# 06_-_DRAM.net
KiCad netlist of a schematic drawn in Altium Designer
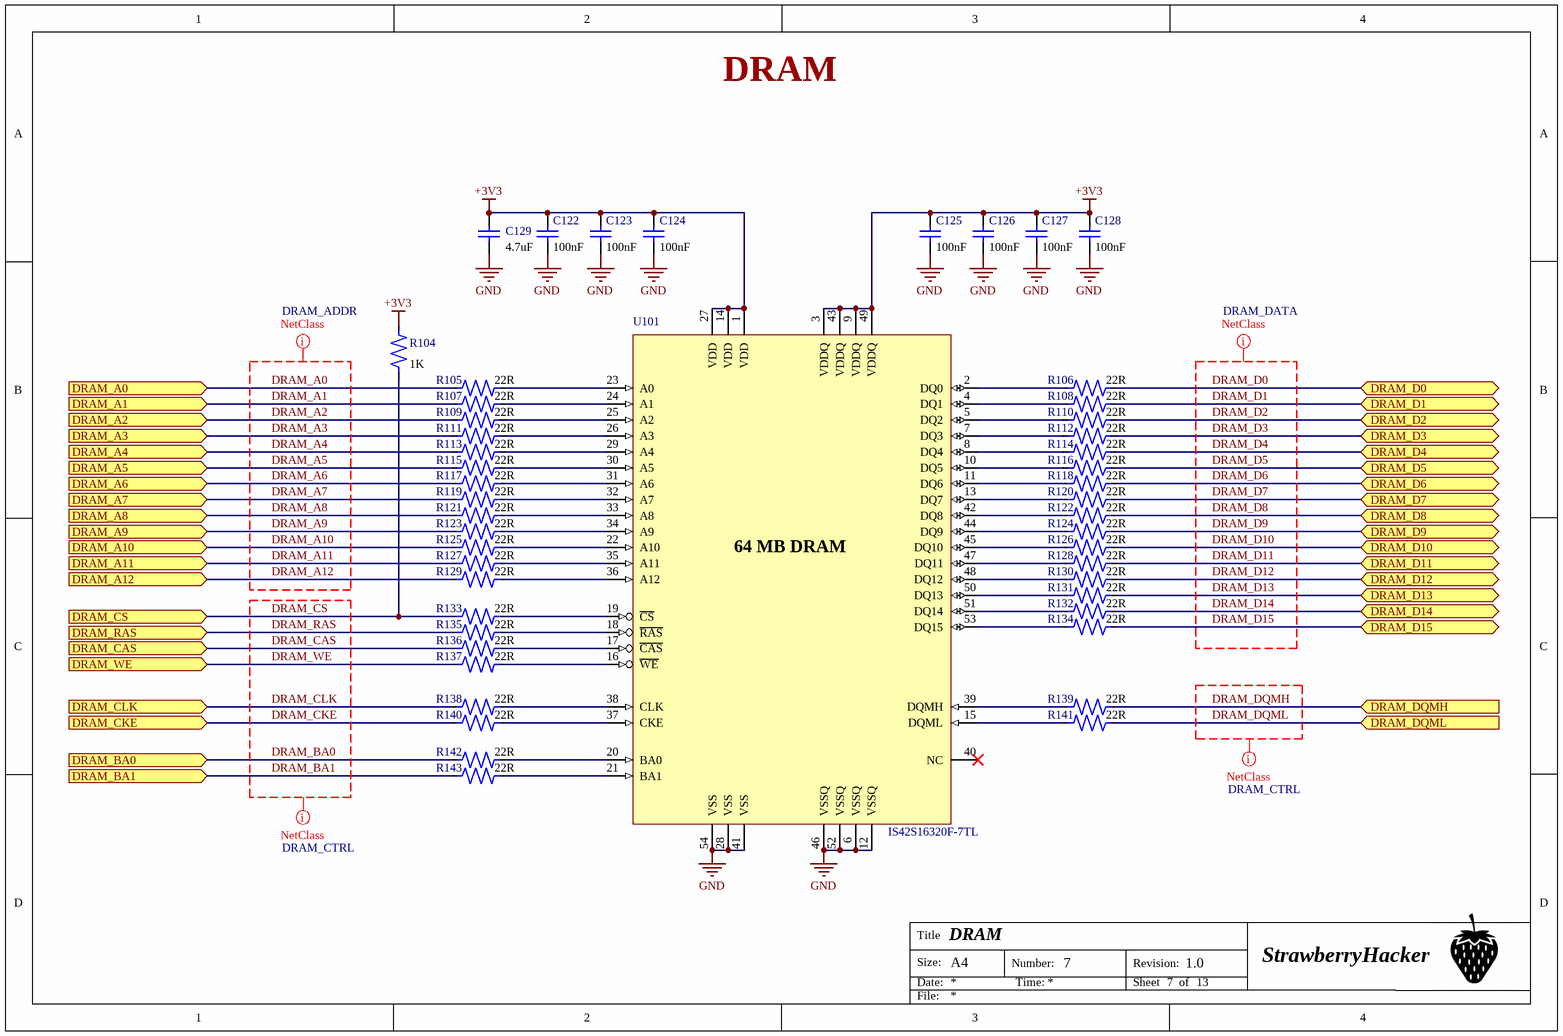
[diagram p0: [06] - DRAM.SchDoc]

(export (version "E")
  (design (tool "Eeschema 10.0.6"))
  (components
    (comp (ref "C122")
      (value "100nF")
      (footprint "C0402")
      (description "C0402")
      (fields (field (name "Comment") "04023C103KAT2A"))
      (libsource (lib "Passive components") (part "04023C103KAT2A"))
    )
    (comp (ref "C123")
      (value "100nF")
      (footprint "C0402")
      (description "C0402")
      (fields (field (name "Comment") "04023C103KAT2A"))
      (libsource (lib "Passive components") (part "04023C103KAT2A"))
    )
    (comp (ref "C124")
      (value "100nF")
      (footprint "C0402")
      (description "C0402")
      (fields (field (name "Comment") "04023C103KAT2A"))
      (libsource (lib "Passive components") (part "04023C103KAT2A"))
    )
    (comp (ref "C125")
      (value "100nF")
      (footprint "C0402")
      (description "C0402")
      (fields (field (name "Comment") "04023C103KAT2A"))
      (libsource (lib "Passive components") (part "04023C103KAT2A"))
    )
    (comp (ref "C126")
      (value "100nF")
      (footprint "C0402")
      (description "C0402")
      (fields (field (name "Comment") "04023C103KAT2A"))
      (libsource (lib "Passive components") (part "04023C103KAT2A"))
    )
    (comp (ref "C127")
      (value "100nF")
      (footprint "C0402")
      (description "C0402")
      (fields (field (name "Comment") "04023C103KAT2A"))
      (libsource (lib "Passive components") (part "04023C103KAT2A"))
    )
    (comp (ref "C128")
      (value "100nF")
      (footprint "C0402")
      (description "C0402")
      (fields (field (name "Comment") "04023C103KAT2A"))
      (libsource (lib "Passive components") (part "04023C103KAT2A"))
    )
    (comp (ref "C129")
      (value "4.7uF")
      (footprint "C0402")
      (description "C0402")
      (fields (field (name "Comment") "04023C103KAT2A"))
      (libsource (lib "Passive components") (part "04023C103KAT2A"))
    )
    (comp (ref "R104")
      (value "1K")
      (footprint "R0402")
      (description "R0402")
      (fields (field (name "Comment") "CRCW04020000Z0ED"))
      (libsource (lib "Passive components") (part "CRCW04020000Z0ED"))
    )
    (comp (ref "R105")
      (value "22R")
      (footprint "R0402")
      (description "R0402")
      (fields (field (name "Comment") "CRCW04020000Z0ED"))
      (libsource (lib "Passive components") (part "CRCW04020000Z0ED"))
    )
    (comp (ref "R106")
      (value "22R")
      (footprint "R0402")
      (description "R0402")
      (fields (field (name "Comment") "CRCW04020000Z0ED"))
      (libsource (lib "Passive components") (part "CRCW04020000Z0ED"))
    )
    (comp (ref "R107")
      (value "22R")
      (footprint "R0402")
      (description "R0402")
      (fields (field (name "Comment") "CRCW04020000Z0ED"))
      (libsource (lib "Passive components") (part "CRCW04020000Z0ED"))
    )
    (comp (ref "R108")
      (value "22R")
      (footprint "R0402")
      (description "R0402")
      (fields (field (name "Comment") "CRCW04020000Z0ED"))
      (libsource (lib "Passive components") (part "CRCW04020000Z0ED"))
    )
    (comp (ref "R109")
      (value "22R")
      (footprint "R0402")
      (description "R0402")
      (fields (field (name "Comment") "CRCW04020000Z0ED"))
      (libsource (lib "Passive components") (part "CRCW04020000Z0ED"))
    )
    (comp (ref "R110")
      (value "22R")
      (footprint "R0402")
      (description "R0402")
      (fields (field (name "Comment") "CRCW04020000Z0ED"))
      (libsource (lib "Passive components") (part "CRCW04020000Z0ED"))
    )
    (comp (ref "R111")
      (value "22R")
      (footprint "R0402")
      (description "R0402")
      (fields (field (name "Comment") "CRCW04020000Z0ED"))
      (libsource (lib "Passive components") (part "CRCW04020000Z0ED"))
    )
    (comp (ref "R112")
      (value "22R")
      (footprint "R0402")
      (description "R0402")
      (fields (field (name "Comment") "CRCW04020000Z0ED"))
      (libsource (lib "Passive components") (part "CRCW04020000Z0ED"))
    )
    (comp (ref "R113")
      (value "22R")
      (footprint "R0402")
      (description "R0402")
      (fields (field (name "Comment") "CRCW04020000Z0ED"))
      (libsource (lib "Passive components") (part "CRCW04020000Z0ED"))
    )
    (comp (ref "R114")
      (value "22R")
      (footprint "R0402")
      (description "R0402")
      (fields (field (name "Comment") "CRCW04020000Z0ED"))
      (libsource (lib "Passive components") (part "CRCW04020000Z0ED"))
    )
    (comp (ref "R115")
      (value "22R")
      (footprint "R0402")
      (description "R0402")
      (fields (field (name "Comment") "CRCW04020000Z0ED"))
      (libsource (lib "Passive components") (part "CRCW04020000Z0ED"))
    )
    (comp (ref "R116")
      (value "22R")
      (footprint "R0402")
      (description "R0402")
      (fields (field (name "Comment") "CRCW04020000Z0ED"))
      (libsource (lib "Passive components") (part "CRCW04020000Z0ED"))
    )
    (comp (ref "R117")
      (value "22R")
      (footprint "R0402")
      (description "R0402")
      (fields (field (name "Comment") "CRCW04020000Z0ED"))
      (libsource (lib "Passive components") (part "CRCW04020000Z0ED"))
    )
    (comp (ref "R118")
      (value "22R")
      (footprint "R0402")
      (description "R0402")
      (fields (field (name "Comment") "CRCW04020000Z0ED"))
      (libsource (lib "Passive components") (part "CRCW04020000Z0ED"))
    )
    (comp (ref "R119")
      (value "22R")
      (footprint "R0402")
      (description "R0402")
      (fields (field (name "Comment") "CRCW04020000Z0ED"))
      (libsource (lib "Passive components") (part "CRCW04020000Z0ED"))
    )
    (comp (ref "R120")
      (value "22R")
      (footprint "R0402")
      (description "R0402")
      (fields (field (name "Comment") "CRCW04020000Z0ED"))
      (libsource (lib "Passive components") (part "CRCW04020000Z0ED"))
    )
    (comp (ref "R121")
      (value "22R")
      (footprint "R0402")
      (description "R0402")
      (fields (field (name "Comment") "CRCW04020000Z0ED"))
      (libsource (lib "Passive components") (part "CRCW04020000Z0ED"))
    )
    (comp (ref "R122")
      (value "22R")
      (footprint "R0402")
      (description "R0402")
      (fields (field (name "Comment") "CRCW04020000Z0ED"))
      (libsource (lib "Passive components") (part "CRCW04020000Z0ED"))
    )
    (comp (ref "R123")
      (value "22R")
      (footprint "R0402")
      (description "R0402")
      (fields (field (name "Comment") "CRCW04020000Z0ED"))
      (libsource (lib "Passive components") (part "CRCW04020000Z0ED"))
    )
    (comp (ref "R124")
      (value "22R")
      (footprint "R0402")
      (description "R0402")
      (fields (field (name "Comment") "CRCW04020000Z0ED"))
      (libsource (lib "Passive components") (part "CRCW04020000Z0ED"))
    )
    (comp (ref "R125")
      (value "22R")
      (footprint "R0402")
      (description "R0402")
      (fields (field (name "Comment") "CRCW04020000Z0ED"))
      (libsource (lib "Passive components") (part "CRCW04020000Z0ED"))
    )
    (comp (ref "R126")
      (value "22R")
      (footprint "R0402")
      (description "R0402")
      (fields (field (name "Comment") "CRCW04020000Z0ED"))
      (libsource (lib "Passive components") (part "CRCW04020000Z0ED"))
    )
    (comp (ref "R127")
      (value "22R")
      (footprint "R0402")
      (description "R0402")
      (fields (field (name "Comment") "CRCW04020000Z0ED"))
      (libsource (lib "Passive components") (part "CRCW04020000Z0ED"))
    )
    (comp (ref "R128")
      (value "22R")
      (footprint "R0402")
      (description "R0402")
      (fields (field (name "Comment") "CRCW04020000Z0ED"))
      (libsource (lib "Passive components") (part "CRCW04020000Z0ED"))
    )
    (comp (ref "R129")
      (value "22R")
      (footprint "R0402")
      (description "R0402")
      (fields (field (name "Comment") "CRCW04020000Z0ED"))
      (libsource (lib "Passive components") (part "CRCW04020000Z0ED"))
    )
    (comp (ref "R130")
      (value "22R")
      (footprint "R0402")
      (description "R0402")
      (fields (field (name "Comment") "CRCW04020000Z0ED"))
      (libsource (lib "Passive components") (part "CRCW04020000Z0ED"))
    )
    (comp (ref "R131")
      (value "22R")
      (footprint "R0402")
      (description "R0402")
      (fields (field (name "Comment") "CRCW04020000Z0ED"))
      (libsource (lib "Passive components") (part "CRCW04020000Z0ED"))
    )
    (comp (ref "R132")
      (value "22R")
      (footprint "R0402")
      (description "R0402")
      (fields (field (name "Comment") "CRCW04020000Z0ED"))
      (libsource (lib "Passive components") (part "CRCW04020000Z0ED"))
    )
    (comp (ref "R133")
      (value "22R")
      (footprint "R0402")
      (description "R0402")
      (fields (field (name "Comment") "CRCW04020000Z0ED"))
      (libsource (lib "Passive components") (part "CRCW04020000Z0ED"))
    )
    (comp (ref "R134")
      (value "22R")
      (footprint "R0402")
      (description "R0402")
      (fields (field (name "Comment") "CRCW04020000Z0ED"))
      (libsource (lib "Passive components") (part "CRCW04020000Z0ED"))
    )
    (comp (ref "R135")
      (value "22R")
      (footprint "R0402")
      (description "R0402")
      (fields (field (name "Comment") "CRCW04020000Z0ED"))
      (libsource (lib "Passive components") (part "CRCW04020000Z0ED"))
    )
    (comp (ref "R136")
      (value "22R")
      (footprint "R0402")
      (description "R0402")
      (fields (field (name "Comment") "CRCW04020000Z0ED"))
      (libsource (lib "Passive components") (part "CRCW04020000Z0ED"))
    )
    (comp (ref "R137")
      (value "22R")
      (footprint "R0402")
      (description "R0402")
      (fields (field (name "Comment") "CRCW04020000Z0ED"))
      (libsource (lib "Passive components") (part "CRCW04020000Z0ED"))
    )
    (comp (ref "R138")
      (value "22R")
      (footprint "R0402")
      (description "R0402")
      (fields (field (name "Comment") "CRCW04020000Z0ED"))
      (libsource (lib "Passive components") (part "CRCW04020000Z0ED"))
    )
    (comp (ref "R139")
      (value "22R")
      (footprint "R0402")
      (description "R0402")
      (fields (field (name "Comment") "CRCW04020000Z0ED"))
      (libsource (lib "Passive components") (part "CRCW04020000Z0ED"))
    )
    (comp (ref "R140")
      (value "22R")
      (footprint "R0402")
      (description "R0402")
      (fields (field (name "Comment") "CRCW04020000Z0ED"))
      (libsource (lib "Passive components") (part "CRCW04020000Z0ED"))
    )
    (comp (ref "R141")
      (value "22R")
      (footprint "R0402")
      (description "R0402")
      (fields (field (name "Comment") "CRCW04020000Z0ED"))
      (libsource (lib "Passive components") (part "CRCW04020000Z0ED"))
    )
    (comp (ref "R142")
      (value "22R")
      (footprint "R0402")
      (description "R0402")
      (fields (field (name "Comment") "CRCW04020000Z0ED"))
      (libsource (lib "Passive components") (part "CRCW04020000Z0ED"))
    )
    (comp (ref "R143")
      (value "22R")
      (footprint "R0402")
      (description "R0402")
      (fields (field (name "Comment") "CRCW04020000Z0ED"))
      (libsource (lib "Passive components") (part "CRCW04020000Z0ED"))
    )
    (comp (ref "U101")
      (value "IS42S16320F-7TL")
      (footprint "IS42S16320F-7TL")
      (description "SDRAM 512Mb 32Mx16 TSOP")
      (libsource (lib "Memory") (part "IS42S16320F-7TL"))
    )
  )
  (nets
    (net (code "1") (name "+3V3") (class "Default")
      (node (ref "C122") (pin "2") (pinfunction "2_2") (pintype "passive"))
      (node (ref "C123") (pin "2") (pinfunction "2_2") (pintype "passive"))
      (node (ref "C124") (pin "2") (pinfunction "2_2") (pintype "passive"))
      (node (ref "C125") (pin "2") (pinfunction "2_2") (pintype "passive"))
      (node (ref "C126") (pin "2") (pinfunction "2_2") (pintype "passive"))
      (node (ref "C127") (pin "2") (pinfunction "2_2") (pintype "passive"))
      (node (ref "C128") (pin "2") (pinfunction "2_2") (pintype "passive"))
      (node (ref "C129") (pin "2") (pinfunction "2_2") (pintype "passive"))
      (node (ref "R104") (pin "2") (pinfunction "3_2") (pintype "passive"))
      (node (ref "U101") (pin "1") (pinfunction "VDD_1") (pintype "power_in"))
      (node (ref "U101") (pin "14") (pinfunction "VDD_14") (pintype "power_in"))
      (node (ref "U101") (pin "27") (pinfunction "VDD_27") (pintype "power_in"))
      (node (ref "U101") (pin "3") (pinfunction "VDDQ_3") (pintype "power_in"))
      (node (ref "U101") (pin "43") (pinfunction "VDDQ_43") (pintype "power_in"))
      (node (ref "U101") (pin "49") (pinfunction "VDDQ_49") (pintype "power_in"))
      (node (ref "U101") (pin "9") (pinfunction "VDDQ_9") (pintype "power_in"))
    )
    (net (code "2") (name "/DRAM_A0") (class "Default")
      (node (ref "R105") (pin "1") (pinfunction "1_1") (pintype "passive"))
    )
    (net (code "3") (name "/DRAM_A1") (class "Default")
      (node (ref "R107") (pin "1") (pinfunction "1_1") (pintype "passive"))
    )
    (net (code "4") (name "/DRAM_A2") (class "Default")
      (node (ref "R109") (pin "1") (pinfunction "1_1") (pintype "passive"))
    )
    (net (code "5") (name "/DRAM_A3") (class "Default")
      (node (ref "R111") (pin "1") (pinfunction "1_1") (pintype "passive"))
    )
    (net (code "6") (name "/DRAM_A4") (class "Default")
      (node (ref "R113") (pin "1") (pinfunction "1_1") (pintype "passive"))
    )
    (net (code "7") (name "/DRAM_A5") (class "Default")
      (node (ref "R115") (pin "1") (pinfunction "1_1") (pintype "passive"))
    )
    (net (code "8") (name "/DRAM_A6") (class "Default")
      (node (ref "R117") (pin "1") (pinfunction "1_1") (pintype "passive"))
    )
    (net (code "9") (name "/DRAM_A7") (class "Default")
      (node (ref "R119") (pin "1") (pinfunction "1_1") (pintype "passive"))
    )
    (net (code "10") (name "/DRAM_A8") (class "Default")
      (node (ref "R121") (pin "1") (pinfunction "1_1") (pintype "passive"))
    )
    (net (code "11") (name "/DRAM_A9") (class "Default")
      (node (ref "R123") (pin "1") (pinfunction "1_1") (pintype "passive"))
    )
    (net (code "12") (name "/DRAM_A10") (class "Default")
      (node (ref "R125") (pin "1") (pinfunction "1_1") (pintype "passive"))
    )
    (net (code "13") (name "/DRAM_A11") (class "Default")
      (node (ref "R127") (pin "1") (pinfunction "1_1") (pintype "passive"))
    )
    (net (code "14") (name "/DRAM_A12") (class "Default")
      (node (ref "R129") (pin "1") (pinfunction "1_1") (pintype "passive"))
    )
    (net (code "15") (name "/DRAM_BA0") (class "Default")
      (node (ref "R142") (pin "1") (pinfunction "1_1") (pintype "passive"))
    )
    (net (code "16") (name "/DRAM_BA1") (class "Default")
      (node (ref "R143") (pin "1") (pinfunction "1_1") (pintype "passive"))
    )
    (net (code "17") (name "/DRAM_CAS") (class "Default")
      (node (ref "R136") (pin "1") (pinfunction "1_1") (pintype "passive"))
    )
    (net (code "18") (name "/DRAM_CKE") (class "Default")
      (node (ref "R140") (pin "1") (pinfunction "1_1") (pintype "passive"))
    )
    (net (code "19") (name "/DRAM_CLK") (class "Default")
      (node (ref "R138") (pin "1") (pinfunction "1_1") (pintype "passive"))
    )
    (net (code "20") (name "/DRAM_CS") (class "Default")
      (node (ref "R104") (pin "1") (pinfunction "1_1") (pintype "passive"))
      (node (ref "R133") (pin "1") (pinfunction "1_1") (pintype "passive"))
    )
    (net (code "21") (name "/DRAM_D0") (class "Default")
      (node (ref "R106") (pin "2") (pinfunction "3_2") (pintype "passive"))
    )
    (net (code "22") (name "/DRAM_D1") (class "Default")
      (node (ref "R108") (pin "2") (pinfunction "3_2") (pintype "passive"))
    )
    (net (code "23") (name "/DRAM_D2") (class "Default")
      (node (ref "R110") (pin "2") (pinfunction "3_2") (pintype "passive"))
    )
    (net (code "24") (name "/DRAM_D3") (class "Default")
      (node (ref "R112") (pin "2") (pinfunction "3_2") (pintype "passive"))
    )
    (net (code "25") (name "/DRAM_D4") (class "Default")
      (node (ref "R114") (pin "2") (pinfunction "3_2") (pintype "passive"))
    )
    (net (code "26") (name "/DRAM_D5") (class "Default")
      (node (ref "R116") (pin "2") (pinfunction "3_2") (pintype "passive"))
    )
    (net (code "27") (name "/DRAM_D6") (class "Default")
      (node (ref "R118") (pin "2") (pinfunction "3_2") (pintype "passive"))
    )
    (net (code "28") (name "/DRAM_D7") (class "Default")
      (node (ref "R120") (pin "2") (pinfunction "3_2") (pintype "passive"))
    )
    (net (code "29") (name "/DRAM_D8") (class "Default")
      (node (ref "R122") (pin "2") (pinfunction "3_2") (pintype "passive"))
    )
    (net (code "30") (name "/DRAM_D9") (class "Default")
      (node (ref "R124") (pin "2") (pinfunction "3_2") (pintype "passive"))
    )
    (net (code "31") (name "/DRAM_D10") (class "Default")
      (node (ref "R126") (pin "2") (pinfunction "3_2") (pintype "passive"))
    )
    (net (code "32") (name "/DRAM_D11") (class "Default")
      (node (ref "R128") (pin "2") (pinfunction "3_2") (pintype "passive"))
    )
    (net (code "33") (name "/DRAM_D12") (class "Default")
      (node (ref "R130") (pin "2") (pinfunction "3_2") (pintype "passive"))
    )
    (net (code "34") (name "/DRAM_D13") (class "Default")
      (node (ref "R131") (pin "2") (pinfunction "3_2") (pintype "passive"))
    )
    (net (code "35") (name "/DRAM_D14") (class "Default")
      (node (ref "R132") (pin "2") (pinfunction "3_2") (pintype "passive"))
    )
    (net (code "36") (name "/DRAM_D15") (class "Default")
      (node (ref "R134") (pin "2") (pinfunction "3_2") (pintype "passive"))
    )
    (net (code "37") (name "/DRAM_DQMH") (class "Default")
      (node (ref "R139") (pin "2") (pinfunction "3_2") (pintype "passive"))
    )
    (net (code "38") (name "/DRAM_DQML") (class "Default")
      (node (ref "R141") (pin "2") (pinfunction "3_2") (pintype "passive"))
    )
    (net (code "39") (name "/DRAM_RAS") (class "Default")
      (node (ref "R135") (pin "1") (pinfunction "1_1") (pintype "passive"))
    )
    (net (code "40") (name "/DRAM_WE") (class "Default")
      (node (ref "R137") (pin "1") (pinfunction "1_1") (pintype "passive"))
    )
    (net (code "41") (name "GND") (class "Default")
      (node (ref "C122") (pin "1") (pinfunction "1_1") (pintype "passive"))
      (node (ref "C123") (pin "1") (pinfunction "1_1") (pintype "passive"))
      (node (ref "C124") (pin "1") (pinfunction "1_1") (pintype "passive"))
      (node (ref "C125") (pin "1") (pinfunction "1_1") (pintype "passive"))
      (node (ref "C126") (pin "1") (pinfunction "1_1") (pintype "passive"))
      (node (ref "C127") (pin "1") (pinfunction "1_1") (pintype "passive"))
      (node (ref "C128") (pin "1") (pinfunction "1_1") (pintype "passive"))
      (node (ref "C129") (pin "1") (pinfunction "1_1") (pintype "passive"))
      (node (ref "U101") (pin "12") (pinfunction "VSSQ_12") (pintype "power_in"))
      (node (ref "U101") (pin "28") (pinfunction "VSS_28") (pintype "power_in"))
      (node (ref "U101") (pin "41") (pinfunction "VSS_41") (pintype "power_in"))
      (node (ref "U101") (pin "46") (pinfunction "VSSQ_46") (pintype "power_in"))
      (node (ref "U101") (pin "52") (pinfunction "VSSQ_52") (pintype "power_in"))
      (node (ref "U101") (pin "54") (pinfunction "VSS_54") (pintype "power_in"))
      (node (ref "U101") (pin "6") (pinfunction "VSSQ_6") (pintype "power_in"))
    )
    (net (code "42") (name "Net-(R105-3)") (class "Default")
      (node (ref "R105") (pin "2") (pinfunction "3_2") (pintype "passive"))
      (node (ref "U101") (pin "23") (pinfunction "A0_23") (pintype "input"))
    )
    (net (code "43") (name "Net-(R107-3)") (class "Default")
      (node (ref "R107") (pin "2") (pinfunction "3_2") (pintype "passive"))
      (node (ref "U101") (pin "24") (pinfunction "A1_24") (pintype "input"))
    )
    (net (code "44") (name "Net-(R109-3)") (class "Default")
      (node (ref "R109") (pin "2") (pinfunction "3_2") (pintype "passive"))
      (node (ref "U101") (pin "25") (pinfunction "A2_25") (pintype "input"))
    )
    (net (code "45") (name "Net-(R111-3)") (class "Default")
      (node (ref "R111") (pin "2") (pinfunction "3_2") (pintype "passive"))
      (node (ref "U101") (pin "26") (pinfunction "A3_26") (pintype "input"))
    )
    (net (code "46") (name "Net-(R113-3)") (class "Default")
      (node (ref "R113") (pin "2") (pinfunction "3_2") (pintype "passive"))
      (node (ref "U101") (pin "29") (pinfunction "A4_29") (pintype "input"))
    )
    (net (code "47") (name "Net-(R115-3)") (class "Default")
      (node (ref "R115") (pin "2") (pinfunction "3_2") (pintype "passive"))
      (node (ref "U101") (pin "30") (pinfunction "A5_30") (pintype "input"))
    )
    (net (code "48") (name "Net-(R117-3)") (class "Default")
      (node (ref "R117") (pin "2") (pinfunction "3_2") (pintype "passive"))
      (node (ref "U101") (pin "31") (pinfunction "A6_31") (pintype "input"))
    )
    (net (code "49") (name "Net-(R119-3)") (class "Default")
      (node (ref "R119") (pin "2") (pinfunction "3_2") (pintype "passive"))
      (node (ref "U101") (pin "32") (pinfunction "A7_32") (pintype "input"))
    )
    (net (code "50") (name "Net-(R121-3)") (class "Default")
      (node (ref "R121") (pin "2") (pinfunction "3_2") (pintype "passive"))
      (node (ref "U101") (pin "33") (pinfunction "A8_33") (pintype "input"))
    )
    (net (code "51") (name "Net-(R123-3)") (class "Default")
      (node (ref "R123") (pin "2") (pinfunction "3_2") (pintype "passive"))
      (node (ref "U101") (pin "34") (pinfunction "A9_34") (pintype "input"))
    )
    (net (code "52") (name "Net-(R125-3)") (class "Default")
      (node (ref "R125") (pin "2") (pinfunction "3_2") (pintype "passive"))
      (node (ref "U101") (pin "22") (pinfunction "A10_22") (pintype "input"))
    )
    (net (code "53") (name "Net-(R127-3)") (class "Default")
      (node (ref "R127") (pin "2") (pinfunction "3_2") (pintype "passive"))
      (node (ref "U101") (pin "35") (pinfunction "A11_35") (pintype "input"))
    )
    (net (code "54") (name "Net-(R129-3)") (class "Default")
      (node (ref "R129") (pin "2") (pinfunction "3_2") (pintype "passive"))
      (node (ref "U101") (pin "36") (pinfunction "A12_36") (pintype "input"))
    )
    (net (code "55") (name "Net-(R133-3)") (class "Default")
      (node (ref "R133") (pin "2") (pinfunction "3_2") (pintype "passive"))
      (node (ref "U101") (pin "19") (pinfunction "~{CS}_19") (pintype "input"))
    )
    (net (code "56") (name "Net-(R135-3)") (class "Default")
      (node (ref "R135") (pin "2") (pinfunction "3_2") (pintype "passive"))
      (node (ref "U101") (pin "18") (pinfunction "~{RAS}_18") (pintype "input"))
    )
    (net (code "57") (name "Net-(R136-3)") (class "Default")
      (node (ref "R136") (pin "2") (pinfunction "3_2") (pintype "passive"))
      (node (ref "U101") (pin "17") (pinfunction "~{CAS}_17") (pintype "input"))
    )
    (net (code "58") (name "Net-(R137-3)") (class "Default")
      (node (ref "R137") (pin "2") (pinfunction "3_2") (pintype "passive"))
      (node (ref "U101") (pin "16") (pinfunction "~{WE}_16") (pintype "input"))
    )
    (net (code "59") (name "Net-(R138-3)") (class "Default")
      (node (ref "R138") (pin "2") (pinfunction "3_2") (pintype "passive"))
      (node (ref "U101") (pin "38") (pinfunction "CLK_38") (pintype "input"))
    )
    (net (code "60") (name "Net-(R140-3)") (class "Default")
      (node (ref "R140") (pin "2") (pinfunction "3_2") (pintype "passive"))
      (node (ref "U101") (pin "37") (pinfunction "CKE_37") (pintype "input"))
    )
    (net (code "61") (name "Net-(R142-3)") (class "Default")
      (node (ref "R142") (pin "2") (pinfunction "3_2") (pintype "passive"))
      (node (ref "U101") (pin "20") (pinfunction "BA0_20") (pintype "input"))
    )
    (net (code "62") (name "Net-(R143-3)") (class "Default")
      (node (ref "R143") (pin "2") (pinfunction "3_2") (pintype "passive"))
      (node (ref "U101") (pin "21") (pinfunction "BA1_21") (pintype "input"))
    )
    (net (code "63") (name "Net-(U101-DQ0)") (class "Default")
      (node (ref "R106") (pin "1") (pinfunction "1_1") (pintype "passive"))
      (node (ref "U101") (pin "2") (pinfunction "DQ0_2") (pintype "bidirectional"))
    )
    (net (code "64") (name "Net-(U101-DQ1)") (class "Default")
      (node (ref "R108") (pin "1") (pinfunction "1_1") (pintype "passive"))
      (node (ref "U101") (pin "4") (pinfunction "DQ1_4") (pintype "bidirectional"))
    )
    (net (code "65") (name "Net-(U101-DQ2)") (class "Default")
      (node (ref "R110") (pin "1") (pinfunction "1_1") (pintype "passive"))
      (node (ref "U101") (pin "5") (pinfunction "DQ2_5") (pintype "bidirectional"))
    )
    (net (code "66") (name "Net-(U101-DQ3)") (class "Default")
      (node (ref "R112") (pin "1") (pinfunction "1_1") (pintype "passive"))
      (node (ref "U101") (pin "7") (pinfunction "DQ3_7") (pintype "bidirectional"))
    )
    (net (code "67") (name "Net-(U101-DQ4)") (class "Default")
      (node (ref "R114") (pin "1") (pinfunction "1_1") (pintype "passive"))
      (node (ref "U101") (pin "8") (pinfunction "DQ4_8") (pintype "bidirectional"))
    )
    (net (code "68") (name "Net-(U101-DQ5)") (class "Default")
      (node (ref "R116") (pin "1") (pinfunction "1_1") (pintype "passive"))
      (node (ref "U101") (pin "10") (pinfunction "DQ5_10") (pintype "bidirectional"))
    )
    (net (code "69") (name "Net-(U101-DQ6)") (class "Default")
      (node (ref "R118") (pin "1") (pinfunction "1_1") (pintype "passive"))
      (node (ref "U101") (pin "11") (pinfunction "DQ6_11") (pintype "bidirectional"))
    )
    (net (code "70") (name "Net-(U101-DQ7)") (class "Default")
      (node (ref "R120") (pin "1") (pinfunction "1_1") (pintype "passive"))
      (node (ref "U101") (pin "13") (pinfunction "DQ7_13") (pintype "bidirectional"))
    )
    (net (code "71") (name "Net-(U101-DQ8)") (class "Default")
      (node (ref "R122") (pin "1") (pinfunction "1_1") (pintype "passive"))
      (node (ref "U101") (pin "42") (pinfunction "DQ8_42") (pintype "bidirectional"))
    )
    (net (code "72") (name "Net-(U101-DQ9)") (class "Default")
      (node (ref "R124") (pin "1") (pinfunction "1_1") (pintype "passive"))
      (node (ref "U101") (pin "44") (pinfunction "DQ9_44") (pintype "bidirectional"))
    )
    (net (code "73") (name "Net-(U101-DQ10)") (class "Default")
      (node (ref "R126") (pin "1") (pinfunction "1_1") (pintype "passive"))
      (node (ref "U101") (pin "45") (pinfunction "DQ10_45") (pintype "bidirectional"))
    )
    (net (code "74") (name "Net-(U101-DQ11)") (class "Default")
      (node (ref "R128") (pin "1") (pinfunction "1_1") (pintype "passive"))
      (node (ref "U101") (pin "47") (pinfunction "DQ11_47") (pintype "bidirectional"))
    )
    (net (code "75") (name "Net-(U101-DQ12)") (class "Default")
      (node (ref "R130") (pin "1") (pinfunction "1_1") (pintype "passive"))
      (node (ref "U101") (pin "48") (pinfunction "DQ12_48") (pintype "bidirectional"))
    )
    (net (code "76") (name "Net-(U101-DQ13)") (class "Default")
      (node (ref "R131") (pin "1") (pinfunction "1_1") (pintype "passive"))
      (node (ref "U101") (pin "50") (pinfunction "DQ13_50") (pintype "bidirectional"))
    )
    (net (code "77") (name "Net-(U101-DQ14)") (class "Default")
      (node (ref "R132") (pin "1") (pinfunction "1_1") (pintype "passive"))
      (node (ref "U101") (pin "51") (pinfunction "DQ14_51") (pintype "bidirectional"))
    )
    (net (code "78") (name "Net-(U101-DQ15)") (class "Default")
      (node (ref "R134") (pin "1") (pinfunction "1_1") (pintype "passive"))
      (node (ref "U101") (pin "53") (pinfunction "DQ15_53") (pintype "bidirectional"))
    )
    (net (code "79") (name "Net-(U101-DQMH)") (class "Default")
      (node (ref "R139") (pin "1") (pinfunction "1_1") (pintype "passive"))
      (node (ref "U101") (pin "39") (pinfunction "DQMH_39") (pintype "input"))
    )
    (net (code "80") (name "Net-(U101-DQML)") (class "Default")
      (node (ref "R141") (pin "1") (pinfunction "1_1") (pintype "passive"))
      (node (ref "U101") (pin "15") (pinfunction "DQML_15") (pintype "input"))
    )
    (net (code "81") (name "unconnected-(U101-NC-Pad40)") (class "Default")
      (node (ref "U101") (pin "40") (pinfunction "NC_40") (pintype "passive+no_connect"))
    )
  )
)
